# XMC4800-ECAT-P1.net
KiCad netlist of a schematic drawn in Altium Designer
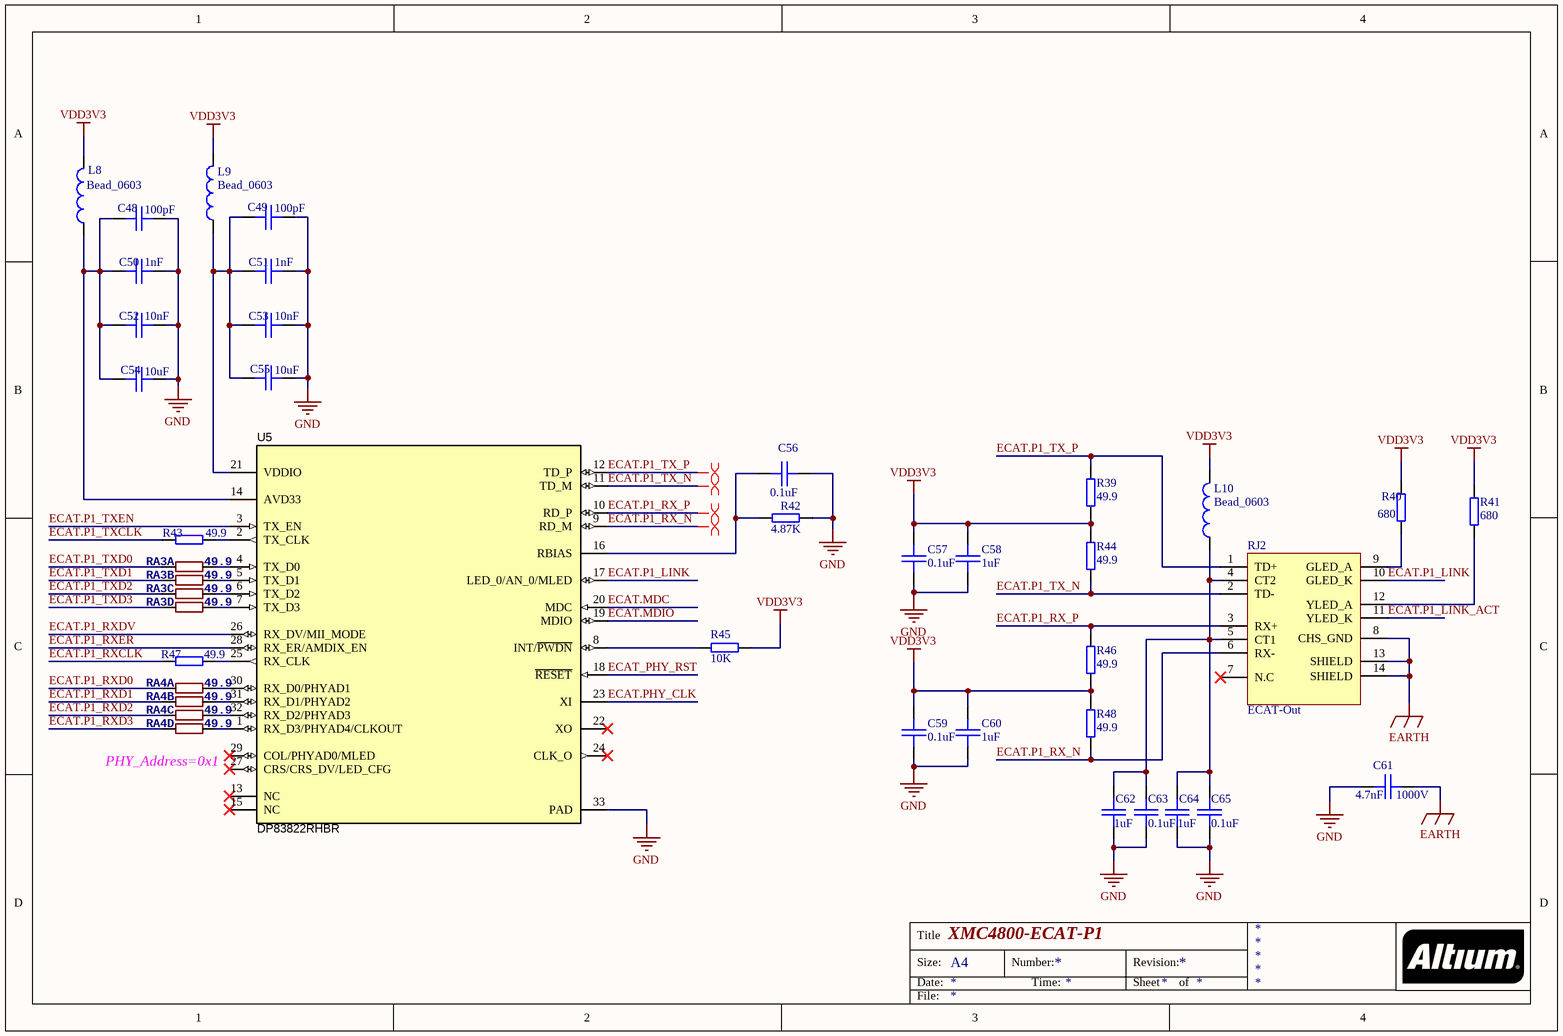
[diagram p0: XMC4800-ECAT-P1.SchDoc]

(export (version "E")
  (design (tool "Eeschema 10.0.6"))
  (components
    (comp (ref "C48")
      (value "100pF")
      (footprint "CAP-0603")
      (description "陶瓷贴片电容0603")
      (fields (field (name "TOLERANCE") "10%") (field (name "VOLTAGE") "50V"))
      (libsource (lib "momo") (part "C_0603"))
    )
    (comp (ref "C49")
      (value "100pF")
      (footprint "CAP-0603")
      (description "陶瓷贴片电容0603")
      (fields (field (name "TOLERANCE") "10%") (field (name "VOLTAGE") "50V"))
      (libsource (lib "momo") (part "C_0603"))
    )
    (comp (ref "C50")
      (value "1nF")
      (footprint "CAP-0603")
      (description "陶瓷贴片电容0603")
      (fields (field (name "TOLERANCE") "10%") (field (name "VOLTAGE") "50V"))
      (libsource (lib "momo") (part "C_0603"))
    )
    (comp (ref "C51")
      (value "1nF")
      (footprint "CAP-0603")
      (description "陶瓷贴片电容0603")
      (fields (field (name "TOLERANCE") "10%") (field (name "VOLTAGE") "50V"))
      (libsource (lib "momo") (part "C_0603"))
    )
    (comp (ref "C52")
      (value "10nF")
      (footprint "CAP-0603")
      (description "陶瓷贴片电容0603")
      (fields (field (name "TOLERANCE") "10%") (field (name "VOLTAGE") "50V"))
      (libsource (lib "momo") (part "C_0603"))
    )
    (comp (ref "C53")
      (value "10nF")
      (footprint "CAP-0603")
      (description "陶瓷贴片电容0603")
      (fields (field (name "TOLERANCE") "10%") (field (name "VOLTAGE") "50V"))
      (libsource (lib "momo") (part "C_0603"))
    )
    (comp (ref "C54")
      (value "10uF")
      (footprint "CAP-0603")
      (description "陶瓷贴片电容0603")
      (fields (field (name "TOLERANCE") "10%") (field (name "VOLTAGE") "50V"))
      (libsource (lib "momo") (part "C_0603"))
    )
    (comp (ref "C55")
      (value "10uF")
      (footprint "CAP-0603")
      (description "陶瓷贴片电容0603")
      (fields (field (name "TOLERANCE") "10%") (field (name "VOLTAGE") "50V"))
      (libsource (lib "momo") (part "C_0603"))
    )
    (comp (ref "C56")
      (value "0.1uF")
      (footprint "CAP-0603")
      (description "陶瓷贴片电容0603")
      (fields (field (name "TOLERANCE") "10%") (field (name "VOLTAGE") "50V"))
      (libsource (lib "momo") (part "C_0603"))
    )
    (comp (ref "C57")
      (value "0.1uF")
      (footprint "CAP-0603")
      (description "陶瓷贴片电容0603")
      (fields (field (name "TOLERANCE") "10%") (field (name "VOLTAGE") "50V"))
      (libsource (lib "momo") (part "C_0603"))
    )
    (comp (ref "C58")
      (value "1uF")
      (footprint "CAP-0603")
      (description "陶瓷贴片电容0603")
      (fields (field (name "TOLERANCE") "10%") (field (name "VOLTAGE") "50V"))
      (libsource (lib "momo") (part "C_0603"))
    )
    (comp (ref "C59")
      (value "0.1uF")
      (footprint "CAP-0603")
      (description "陶瓷贴片电容0603")
      (fields (field (name "TOLERANCE") "10%") (field (name "VOLTAGE") "50V"))
      (libsource (lib "momo") (part "C_0603"))
    )
    (comp (ref "C60")
      (value "1uF")
      (footprint "CAP-0603")
      (description "陶瓷贴片电容0603")
      (fields (field (name "TOLERANCE") "10%") (field (name "VOLTAGE") "50V"))
      (libsource (lib "momo") (part "C_0603"))
    )
    (comp (ref "C61")
      (value "4.7nF")
      (footprint "CAP-1206")
      (description "陶瓷贴片电容1206")
      (fields (field (name "TOLERANCE") "10%") (field (name "VOLTAGE") "1000V"))
      (libsource (lib "momo") (part "C_1206"))
    )
    (comp (ref "C62")
      (value "1uF")
      (footprint "CAP-0603")
      (description "陶瓷贴片电容0603")
      (fields (field (name "TOLERANCE") "10%") (field (name "VOLTAGE") "50V"))
      (libsource (lib "momo") (part "C_0603"))
    )
    (comp (ref "C63")
      (value "0.1uF")
      (footprint "CAP-0603")
      (description "陶瓷贴片电容0603")
      (fields (field (name "TOLERANCE") "10%") (field (name "VOLTAGE") "50V"))
      (libsource (lib "momo") (part "C_0603"))
    )
    (comp (ref "C64")
      (value "1uF")
      (footprint "CAP-0603")
      (description "陶瓷贴片电容0603")
      (fields (field (name "TOLERANCE") "10%") (field (name "VOLTAGE") "50V"))
      (libsource (lib "momo") (part "C_0603"))
    )
    (comp (ref "C65")
      (value "0.1uF")
      (footprint "CAP-0603")
      (description "陶瓷贴片电容0603")
      (fields (field (name "TOLERANCE") "10%") (field (name "VOLTAGE") "50V"))
      (libsource (lib "momo") (part "C_0603"))
    )
    (comp (ref "L8")
      (value "Bead_0603")
      (footprint "L-0603")
      (description "贴片磁珠0603")
      (libsource (lib "momo") (part "Bead_0603"))
    )
    (comp (ref "L9")
      (value "Bead_0603")
      (footprint "L-0603")
      (description "贴片磁珠0603")
      (libsource (lib "momo") (part "Bead_0603"))
    )
    (comp (ref "L10")
      (value "Bead_0603")
      (footprint "L-0603")
      (description "贴片磁珠0603")
      (libsource (lib "momo") (part "Bead_0603"))
    )
    (comp (ref "R39")
      (value "49.9")
      (footprint "RES-0603")
      (description "贴片电阻0603")
      (fields (field (name "TOLERANCE") "5%") (field (name "VOLTAGE") "50V"))
      (libsource (lib "momo") (part "R_0603"))
    )
    (comp (ref "R40")
      (value "680")
      (footprint "RES-0603")
      (description "贴片电阻0603")
      (fields (field (name "TOLERANCE") "5%") (field (name "VOLTAGE") "50V"))
      (libsource (lib "momo") (part "R_0603"))
    )
    (comp (ref "R41")
      (value "680")
      (footprint "RES-0603")
      (description "贴片电阻0603")
      (fields (field (name "TOLERANCE") "5%") (field (name "VOLTAGE") "50V"))
      (libsource (lib "momo") (part "R_0603"))
    )
    (comp (ref "R42")
      (value "4.87K")
      (footprint "RES-0603")
      (description "贴片电阻0603")
      (fields (field (name "TOLERANCE") "5%") (field (name "VOLTAGE") "50V"))
      (libsource (lib "momo") (part "R_0603"))
    )
    (comp (ref "R43")
      (value "49.9")
      (footprint "RES-0603")
      (description "贴片电阻0603")
      (fields (field (name "TOLERANCE") "5%") (field (name "VOLTAGE") "50V"))
      (libsource (lib "momo") (part "R_0603"))
    )
    (comp (ref "R44")
      (value "49.9")
      (footprint "RES-0603")
      (description "贴片电阻0603")
      (fields (field (name "TOLERANCE") "5%") (field (name "VOLTAGE") "50V"))
      (libsource (lib "momo") (part "R_0603"))
    )
    (comp (ref "R45")
      (value "10K")
      (footprint "RES-0603")
      (description "贴片电阻0603")
      (fields (field (name "TOLERANCE") "5%") (field (name "VOLTAGE") "50V"))
      (libsource (lib "momo") (part "R_0603"))
    )
    (comp (ref "R46")
      (value "49.9")
      (footprint "RES-0603")
      (description "贴片电阻0603")
      (fields (field (name "TOLERANCE") "5%") (field (name "VOLTAGE") "50V"))
      (libsource (lib "momo") (part "R_0603"))
    )
    (comp (ref "R47")
      (value "49.9")
      (footprint "RES-0603")
      (description "贴片电阻0603")
      (fields (field (name "TOLERANCE") "5%") (field (name "VOLTAGE") "50V"))
      (libsource (lib "momo") (part "R_0603"))
    )
    (comp (ref "R48")
      (value "49.9")
      (footprint "RES-0603")
      (description "贴片电阻0603")
      (fields (field (name "TOLERANCE") "5%") (field (name "VOLTAGE") "50V"))
      (libsource (lib "momo") (part "R_0603"))
    )
    (comp (ref "RA3")
      (value "49.9")
      (footprint "LC-0603_Rx4")
      (description "排阻")
      (libsource (lib "momo") (part "RS_ARR4"))
    )
    (comp (ref "RA4")
      (value "49.9")
      (footprint "LC-0603_Rx4")
      (description "排阻")
      (libsource (lib "momo") (part "RS_ARR4"))
    )
    (comp (ref "RJ2")
      (value "ECAT-Out")
      (footprint "momo:HR911105A")
      (description "Output")
      (fields (field (name "PUBLISHER") "Altium Limited"))
      (libsource (lib "momo") (part "HR911105A"))
    )
    (comp (ref "U5")
      (value "DP83822RHBR")
      (footprint "RHB0032B")
      (description "10/100 Ethernet PHY, RHB0032B")
      (fields
        (field (name "ALTERNATE PARTNUMBER") "DP83822RHBT")
        (field (name "MANUFACTURER") "Texas Instruments")
        (field (name "SYMBOLCREATOR") "Altium")
        (field (name "PUBLISHER") "Texas Instruments")
      )
      (libsource (lib "momo") (part "DP83822RHBR"))
    )
  )
  (nets
    (net (code "1") (name "/ECAT.MDC") (class "Default")
      (node (ref "U5") (pin "20") (pinfunction "MDC_20") (pintype "input"))
    )
    (net (code "2") (name "/ECAT.MDIO") (class "Default")
      (node (ref "U5") (pin "19") (pinfunction "MDIO_19") (pintype "bidirectional"))
    )
    (net (code "3") (name "/ECAT.P1_LINK") (class "Default")
      (node (ref "RJ2") (pin "10") (pinfunction "GLED_K_10") (pintype "passive"))
      (node (ref "U5") (pin "17") (pinfunction "LED_0/AN_0/MLED_17") (pintype "bidirectional"))
    )
    (net (code "4") (name "/ECAT.P1_LINK_ACT") (class "Default")
      (node (ref "RJ2") (pin "11") (pinfunction "YLED_K_11") (pintype "passive"))
    )
    (net (code "5") (name "/ECAT.P1_RXCLK") (class "Default")
      (node (ref "R47") (pin "1") (pinfunction "1_1") (pintype "passive"))
    )
    (net (code "6") (name "/ECAT.P1_RXD0") (class "Default")
      (node (ref "RA4") (pin "1") (pinfunction "1_1") (pintype "passive"))
    )
    (net (code "7") (name "/ECAT.P1_RXD1") (class "Default")
      (node (ref "RA4") (pin "2") (pinfunction "1_2") (pintype "passive"))
    )
    (net (code "8") (name "/ECAT.P1_RXD2") (class "Default")
      (node (ref "RA4") (pin "3") (pinfunction "1_3") (pintype "passive"))
    )
    (net (code "9") (name "/ECAT.P1_RXD3") (class "Default")
      (node (ref "RA4") (pin "4") (pinfunction "1_4") (pintype "passive"))
    )
    (net (code "10") (name "/ECAT.P1_RXDV") (class "Default")
      (node (ref "U5") (pin "26") (pinfunction "RX_DV/MII_MODE_26") (pintype "bidirectional"))
    )
    (net (code "11") (name "/ECAT.P1_RXER") (class "Default")
      (node (ref "U5") (pin "28") (pinfunction "RX_ER/AMDIX_EN_28") (pintype "bidirectional"))
    )
    (net (code "12") (name "/ECAT.P1_RX_N") (class "Default")
      (node (ref "R48") (pin "1") (pinfunction "1_1") (pintype "passive"))
      (node (ref "RJ2") (pin "6") (pinfunction "RX-_6") (pintype "passive"))
      (node (ref "U5") (pin "9") (pinfunction "RD_M_9") (pintype "bidirectional"))
    )
    (net (code "13") (name "/ECAT.P1_RX_P") (class "Default")
      (node (ref "R46") (pin "2") (pinfunction "2_2") (pintype "passive"))
      (node (ref "RJ2") (pin "3") (pinfunction "RX+_3") (pintype "passive"))
      (node (ref "U5") (pin "10") (pinfunction "RD_P_10") (pintype "bidirectional"))
    )
    (net (code "14") (name "/ECAT.P1_TXCLK") (class "Default")
      (node (ref "R43") (pin "1") (pinfunction "1_1") (pintype "passive"))
    )
    (net (code "15") (name "/ECAT.P1_TXD0") (class "Default")
      (node (ref "RA3") (pin "1") (pinfunction "1_1") (pintype "passive"))
    )
    (net (code "16") (name "/ECAT.P1_TXD1") (class "Default")
      (node (ref "RA3") (pin "2") (pinfunction "1_2") (pintype "passive"))
    )
    (net (code "17") (name "/ECAT.P1_TXD2") (class "Default")
      (node (ref "RA3") (pin "3") (pinfunction "1_3") (pintype "passive"))
    )
    (net (code "18") (name "/ECAT.P1_TXD3") (class "Default")
      (node (ref "RA3") (pin "4") (pinfunction "1_4") (pintype "passive"))
    )
    (net (code "19") (name "/ECAT.P1_TXEN") (class "Default")
      (node (ref "U5") (pin "3") (pinfunction "TX_EN_3") (pintype "input"))
    )
    (net (code "20") (name "/ECAT.P1_TX_N") (class "Default")
      (node (ref "R44") (pin "1") (pinfunction "1_1") (pintype "passive"))
      (node (ref "RJ2") (pin "2") (pinfunction "TD-_2") (pintype "passive"))
      (node (ref "U5") (pin "11") (pinfunction "TD_M_11") (pintype "bidirectional"))
    )
    (net (code "21") (name "/ECAT.P1_TX_P") (class "Default")
      (node (ref "R39") (pin "2") (pinfunction "2_2") (pintype "passive"))
      (node (ref "RJ2") (pin "1") (pinfunction "TD+_1") (pintype "passive"))
      (node (ref "U5") (pin "12") (pinfunction "TD_P_12") (pintype "bidirectional"))
    )
    (net (code "22") (name "/ECAT.PHY_CLK") (class "Default")
      (node (ref "U5") (pin "23") (pinfunction "XI_23") (pintype "passive"))
    )
    (net (code "23") (name "/ECAT_PHY_RST") (class "Default")
      (node (ref "U5") (pin "18") (pinfunction "RESET_18") (pintype "input"))
    )
    (net (code "24") (name "EARTH") (class "Default")
      (node (ref "C61") (pin "2") (pinfunction "2_2") (pintype "passive"))
      (node (ref "RJ2") (pin "13") (pinfunction "SHIELD_13") (pintype "power_in"))
      (node (ref "RJ2") (pin "14") (pinfunction "SHIELD_14") (pintype "power_in"))
      (node (ref "RJ2") (pin "8") (pinfunction "CHS_GND_8") (pintype "passive"))
    )
    (net (code "25") (name "GND") (class "Default")
      (node (ref "C48") (pin "2") (pinfunction "2_2") (pintype "passive"))
      (node (ref "C49") (pin "2") (pinfunction "2_2") (pintype "passive"))
      (node (ref "C50") (pin "1") (pinfunction "1_1") (pintype "passive"))
      (node (ref "C51") (pin "1") (pinfunction "1_1") (pintype "passive"))
      (node (ref "C52") (pin "1") (pinfunction "1_1") (pintype "passive"))
      (node (ref "C53") (pin "1") (pinfunction "1_1") (pintype "passive"))
      (node (ref "C54") (pin "1") (pinfunction "1_1") (pintype "passive"))
      (node (ref "C55") (pin "1") (pinfunction "1_1") (pintype "passive"))
      (node (ref "C56") (pin "2") (pinfunction "2_2") (pintype "passive"))
      (node (ref "C57") (pin "2") (pinfunction "2_2") (pintype "passive"))
      (node (ref "C58") (pin "2") (pinfunction "2_2") (pintype "passive"))
      (node (ref "C59") (pin "2") (pinfunction "2_2") (pintype "passive"))
      (node (ref "C60") (pin "2") (pinfunction "2_2") (pintype "passive"))
      (node (ref "C61") (pin "1") (pinfunction "1_1") (pintype "passive"))
      (node (ref "C62") (pin "2") (pinfunction "2_2") (pintype "passive"))
      (node (ref "C63") (pin "2") (pinfunction "2_2") (pintype "passive"))
      (node (ref "C64") (pin "2") (pinfunction "2_2") (pintype "passive"))
      (node (ref "C65") (pin "2") (pinfunction "2_2") (pintype "passive"))
      (node (ref "R42") (pin "2") (pinfunction "2_2") (pintype "passive"))
      (node (ref "U5") (pin "33") (pinfunction "PAD_33") (pintype "power_in"))
    )
    (net (code "26") (name "Net-(RA3A-2)") (class "Default")
      (node (ref "RA3") (pin "8") (pinfunction "2_8") (pintype "passive"))
      (node (ref "U5") (pin "4") (pinfunction "TX_D0_4") (pintype "input"))
    )
    (net (code "27") (name "Net-(RA3B-2)") (class "Default")
      (node (ref "RA3") (pin "7") (pinfunction "2_7") (pintype "passive"))
      (node (ref "U5") (pin "5") (pinfunction "TX_D1_5") (pintype "input"))
    )
    (net (code "28") (name "Net-(RA3C-2)") (class "Default")
      (node (ref "RA3") (pin "6") (pinfunction "2_6") (pintype "passive"))
      (node (ref "U5") (pin "6") (pinfunction "TX_D2_6") (pintype "input"))
    )
    (net (code "29") (name "Net-(RA3D-2)") (class "Default")
      (node (ref "RA3") (pin "5") (pinfunction "2_5") (pintype "passive"))
      (node (ref "U5") (pin "7") (pinfunction "TX_D3_7") (pintype "input"))
    )
    (net (code "30") (name "Net-(RA4A-2)") (class "Default")
      (node (ref "RA4") (pin "8") (pinfunction "2_8") (pintype "passive"))
      (node (ref "U5") (pin "30") (pinfunction "RX_D0/PHYAD1_30") (pintype "bidirectional"))
    )
    (net (code "31") (name "Net-(RA4B-2)") (class "Default")
      (node (ref "RA4") (pin "7") (pinfunction "2_7") (pintype "passive"))
      (node (ref "U5") (pin "31") (pinfunction "RX_D1/PHYAD2_31") (pintype "bidirectional"))
    )
    (net (code "32") (name "Net-(RA4C-2)") (class "Default")
      (node (ref "RA4") (pin "6") (pinfunction "2_6") (pintype "passive"))
      (node (ref "U5") (pin "32") (pinfunction "RX_D2/PHYAD3_32") (pintype "bidirectional"))
    )
    (net (code "33") (name "Net-(RA4D-2)") (class "Default")
      (node (ref "RA4") (pin "5") (pinfunction "2_5") (pintype "passive"))
      (node (ref "U5") (pin "1") (pinfunction "RX_D3/PHYAD4/CLKOUT_1") (pintype "bidirectional"))
    )
    (net (code "34") (name "Net-(RJ2-CT1)") (class "Default")
      (node (ref "C62") (pin "1") (pinfunction "1_1") (pintype "passive"))
      (node (ref "C63") (pin "1") (pinfunction "1_1") (pintype "passive"))
      (node (ref "C64") (pin "1") (pinfunction "1_1") (pintype "passive"))
      (node (ref "C65") (pin "1") (pinfunction "1_1") (pintype "passive"))
      (node (ref "L10") (pin "1") (pinfunction "1_1") (pintype "passive"))
      (node (ref "RJ2") (pin "4") (pinfunction "CT2_4") (pintype "passive"))
      (node (ref "RJ2") (pin "5") (pinfunction "CT1_5") (pintype "passive"))
    )
    (net (code "35") (name "Net-(RJ2-GLED_A)") (class "Default")
      (node (ref "R40") (pin "1") (pinfunction "1_1") (pintype "passive"))
      (node (ref "RJ2") (pin "9") (pinfunction "GLED_A_9") (pintype "passive"))
    )
    (net (code "36") (name "Net-(RJ2-YLED_A)") (class "Default")
      (node (ref "R41") (pin "2") (pinfunction "2_2") (pintype "passive"))
      (node (ref "RJ2") (pin "12") (pinfunction "YLED_A_12") (pintype "passive"))
    )
    (net (code "37") (name "Net-(U5-AVD33)") (class "Default")
      (node (ref "C48") (pin "1") (pinfunction "1_1") (pintype "passive"))
      (node (ref "C50") (pin "2") (pinfunction "2_2") (pintype "passive"))
      (node (ref "C52") (pin "2") (pinfunction "2_2") (pintype "passive"))
      (node (ref "C54") (pin "2") (pinfunction "2_2") (pintype "passive"))
      (node (ref "L8") (pin "1") (pinfunction "1_1") (pintype "passive"))
      (node (ref "U5") (pin "14") (pinfunction "AVD33_14") (pintype "power_in"))
    )
    (net (code "38") (name "Net-(U5-INT{slash}~{PWDN})") (class "Default")
      (node (ref "R45") (pin "1") (pinfunction "1_1") (pintype "passive"))
      (node (ref "U5") (pin "8") (pinfunction "INT/~{PWDN}_8") (pintype "bidirectional"))
    )
    (net (code "39") (name "Net-(U5-RBIAS)") (class "Default")
      (node (ref "C56") (pin "1") (pinfunction "1_1") (pintype "passive"))
      (node (ref "R42") (pin "1") (pinfunction "1_1") (pintype "passive"))
      (node (ref "U5") (pin "16") (pinfunction "RBIAS_16") (pintype "passive"))
    )
    (net (code "40") (name "Net-(U5-RX_CLK)") (class "Default")
      (node (ref "R47") (pin "2") (pinfunction "2_2") (pintype "passive"))
      (node (ref "U5") (pin "25") (pinfunction "RX_CLK_25") (pintype "output"))
    )
    (net (code "41") (name "Net-(U5-TX_CLK)") (class "Default")
      (node (ref "R43") (pin "2") (pinfunction "2_2") (pintype "passive"))
      (node (ref "U5") (pin "2") (pinfunction "TX_CLK_2") (pintype "output"))
    )
    (net (code "42") (name "Net-(U5-VDDIO)") (class "Default")
      (node (ref "C49") (pin "1") (pinfunction "1_1") (pintype "passive"))
      (node (ref "C51") (pin "2") (pinfunction "2_2") (pintype "passive"))
      (node (ref "C53") (pin "2") (pinfunction "2_2") (pintype "passive"))
      (node (ref "C55") (pin "2") (pinfunction "2_2") (pintype "passive"))
      (node (ref "L9") (pin "1") (pinfunction "1_1") (pintype "passive"))
      (node (ref "U5") (pin "21") (pinfunction "VDDIO_21") (pintype "power_in"))
    )
    (net (code "43") (name "VDD3V3") (class "Default")
      (node (ref "C57") (pin "1") (pinfunction "1_1") (pintype "passive"))
      (node (ref "C58") (pin "1") (pinfunction "1_1") (pintype "passive"))
      (node (ref "C59") (pin "1") (pinfunction "1_1") (pintype "passive"))
      (node (ref "C60") (pin "1") (pinfunction "1_1") (pintype "passive"))
      (node (ref "L10") (pin "2") (pinfunction "2_2") (pintype "passive"))
      (node (ref "L8") (pin "2") (pinfunction "2_2") (pintype "passive"))
      (node (ref "L9") (pin "2") (pinfunction "2_2") (pintype "passive"))
      (node (ref "R39") (pin "1") (pinfunction "1_1") (pintype "passive"))
      (node (ref "R40") (pin "2") (pinfunction "2_2") (pintype "passive"))
      (node (ref "R41") (pin "1") (pinfunction "1_1") (pintype "passive"))
      (node (ref "R44") (pin "2") (pinfunction "2_2") (pintype "passive"))
      (node (ref "R45") (pin "2") (pinfunction "2_2") (pintype "passive"))
      (node (ref "R46") (pin "1") (pinfunction "1_1") (pintype "passive"))
      (node (ref "R48") (pin "2") (pinfunction "2_2") (pintype "passive"))
    )
    (net (code "44") (name "unconnected-(RJ2-N.C-Pad7)") (class "Default")
      (node (ref "RJ2") (pin "7") (pinfunction "N.C_7") (pintype "passive+no_connect"))
    )
    (net (code "45") (name "unconnected-(U5-CLK_O-Pad24)") (class "Default")
      (node (ref "U5") (pin "24") (pinfunction "CLK_O_24") (pintype "output+no_connect"))
    )
    (net (code "46") (name "unconnected-(U5-COL{slash}PHYAD0{slash}MLED-Pad29)") (class "Default")
      (node (ref "U5") (pin "29") (pinfunction "COL/PHYAD0/MLED_29") (pintype "bidirectional+no_connect"))
    )
    (net (code "47") (name "unconnected-(U5-CRS{slash}CRS_DV{slash}LED_CFG-Pad27)") (class "Default")
      (node (ref "U5") (pin "27") (pinfunction "CRS/CRS_DV/LED_CFG_27") (pintype "bidirectional+no_connect"))
    )
    (net (code "48") (name "unconnected-(U5-NC-Pad13)") (class "Default")
      (node (ref "U5") (pin "13") (pinfunction "NC_13") (pintype "passive+no_connect"))
    )
    (net (code "49") (name "unconnected-(U5-NC-Pad15)") (class "Default")
      (node (ref "U5") (pin "15") (pinfunction "NC_15") (pintype "passive+no_connect"))
    )
    (net (code "50") (name "unconnected-(U5-XO-Pad22)") (class "Default")
      (node (ref "U5") (pin "22") (pinfunction "XO_22") (pintype "passive+no_connect"))
    )
  )
)
